# SENSEBREAST.net
KiCad netlist of a schematic drawn in EAGLE
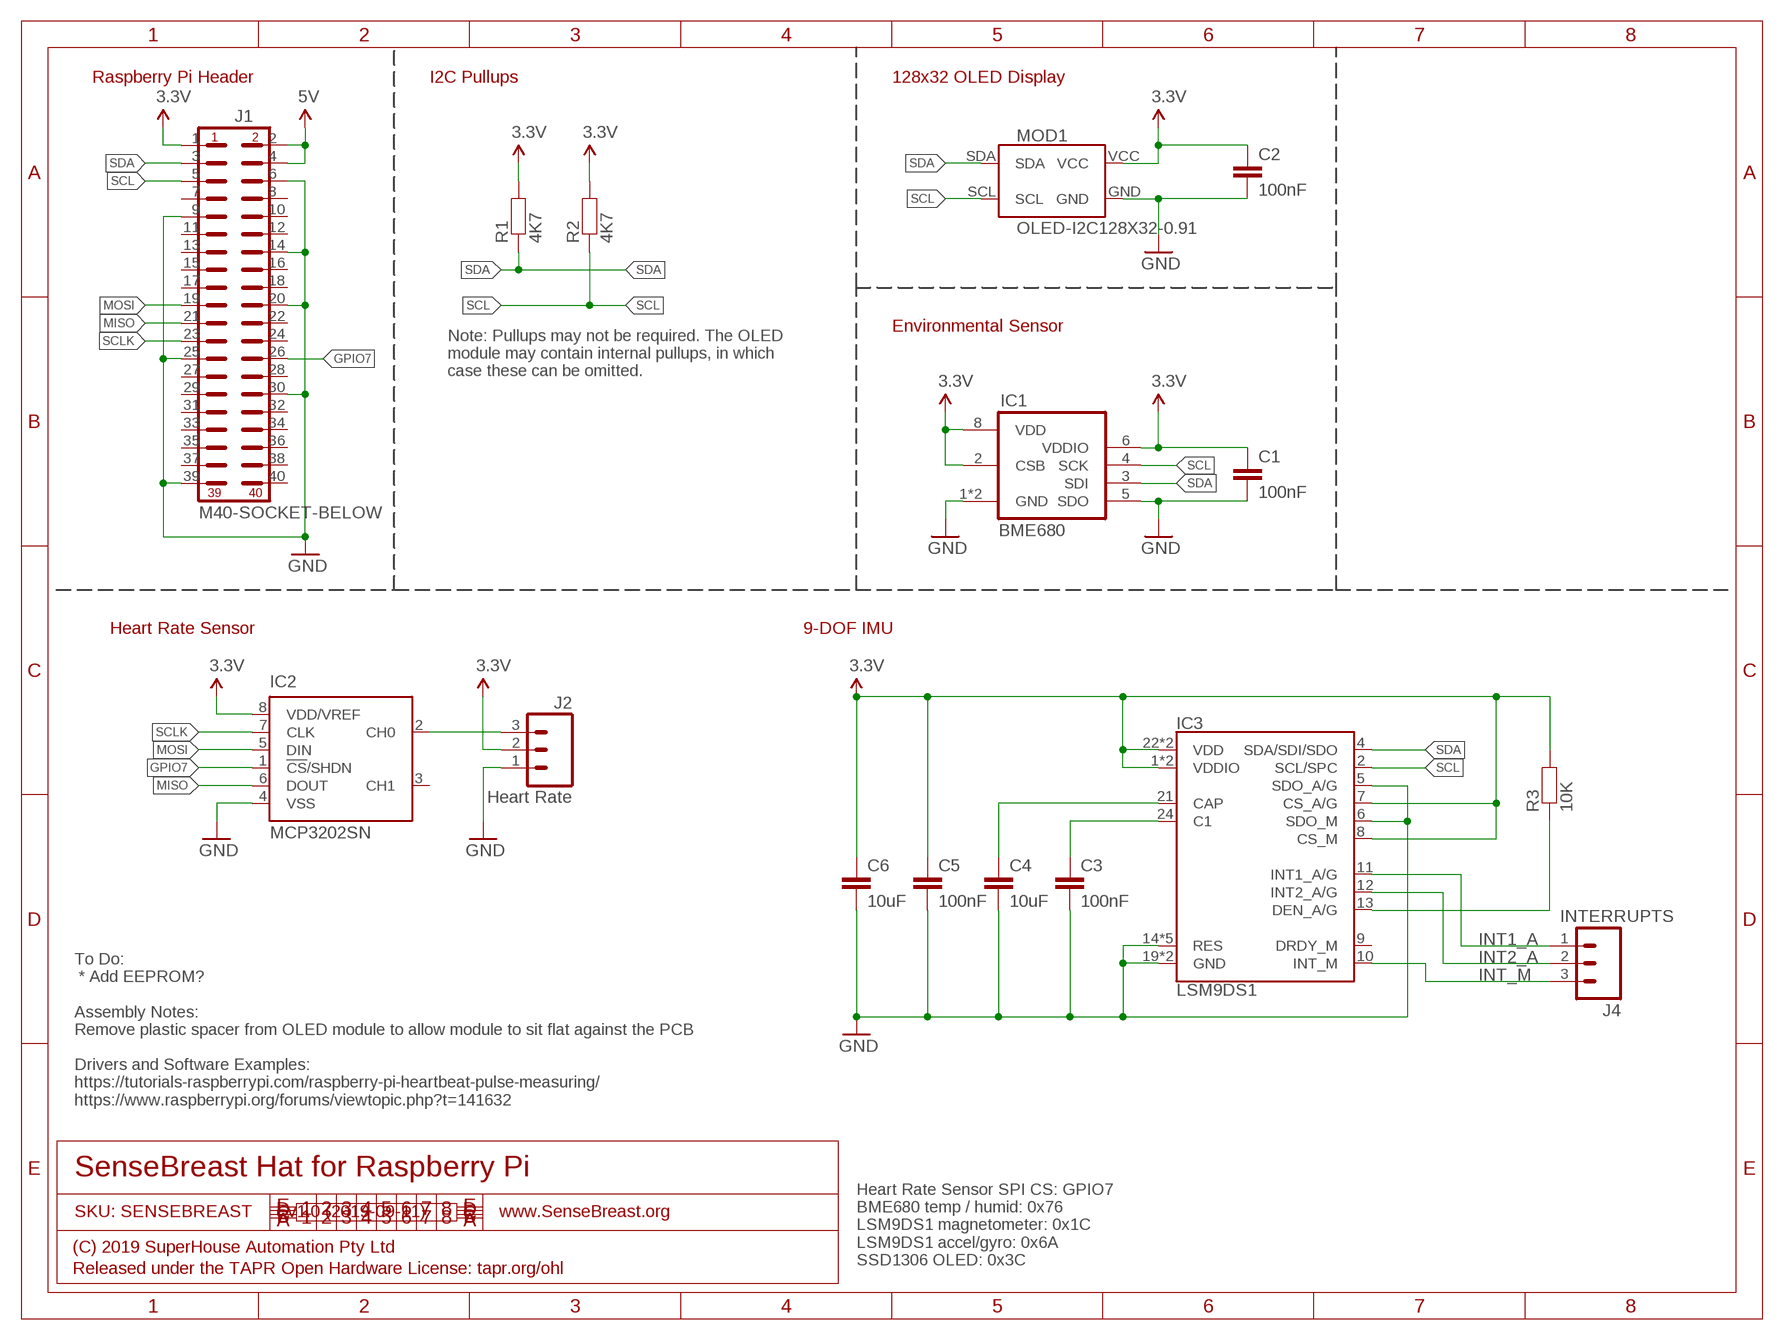
[diagram p0: schematic, sheet 1]

(export (version "E")
  (design (tool "Eeschema 10.0.6"))
  (components
    (comp (ref "C1")
      (value "100nF")
      (footprint "eagle-import:C0603")
      (libsource (lib "eagle-import") (part "CAP0603"))
    )
    (comp (ref "C2")
      (value "100nF")
      (footprint "eagle-import:C0603")
      (libsource (lib "eagle-import") (part "CAP0603"))
    )
    (comp (ref "C3")
      (value "100nF")
      (footprint "eagle-import:C0603")
      (libsource (lib "eagle-import") (part "CAP0603"))
    )
    (comp (ref "C4")
      (value "10uF")
      (footprint "eagle-import:C0805")
      (libsource (lib "eagle-import") (part "CAP0805"))
    )
    (comp (ref "C5")
      (value "100nF")
      (footprint "eagle-import:C0603")
      (libsource (lib "eagle-import") (part "CAP0603"))
    )
    (comp (ref "C6")
      (value "10uF")
      (footprint "eagle-import:C0805")
      (libsource (lib "eagle-import") (part "CAP0805"))
    )
    (comp (ref "IC1")
      (value "BME680")
      (footprint "eagle-import:BME680")
      (libsource (lib "eagle-import") (part "BME680"))
    )
    (comp (ref "IC2")
      (value "MCP3202SN")
      (footprint "eagle-import:SO-08")
      (fields (field (name "MF") "MICROCHIP") (field (name "MPN") "MCP3202-CI/SN"))
      (libsource (lib "eagle-import") (part "MCP3202SN"))
    )
    (comp (ref "IC3")
      (value "LSM9DS1")
      (footprint "eagle-import:LGA24-8X4")
      (libsource (lib "eagle-import") (part "LSM9DS1"))
    )
    (comp (ref "J1")
      (value "M40-SOCKET-BELOW")
      (footprint "eagle-import:2X20-S-BELOW")
      (libsource (lib "eagle-import") (part "M40-SOCKET-BELOW"))
    )
    (comp (ref "J2")
      (value "Heart Rate")
      (footprint "eagle-import:1X03-S-RA")
      (libsource (lib "eagle-import") (part "M03-SOCKET-RIGHTANGLE"))
    )
    (comp (ref "J4")
      (value "INTERRUPTS")
      (footprint "eagle-import:1X03")
      (libsource (lib "eagle-import") (part "M03-PLAIN"))
    )
    (comp (ref "MOD1")
      (value "OLED-I2C128X32-0.91")
      (footprint "eagle-import:OLED-128X32-0.91")
      (libsource (lib "eagle-import") (part "OLED-I2C128X32-0.91"))
    )
    (comp (ref "R1")
      (value "4K7")
      (footprint "eagle-import:R0603")
      (libsource (lib "eagle-import") (part "RESISTOR0603"))
    )
    (comp (ref "R2")
      (value "4K7")
      (footprint "eagle-import:R0603")
      (libsource (lib "eagle-import") (part "RESISTOR0603"))
    )
    (comp (ref "R3")
      (value "10K")
      (footprint "eagle-import:R0603")
      (libsource (lib "eagle-import") (part "RESISTOR0603"))
    )
  )
  (nets
    (net (code "1") (name "/INT1_A") (class "Default")
      (node (ref "IC3") (pin "11") (pinfunction "INT1_A/G_11") (pintype "bidirectional"))
      (node (ref "J4") (pin "1") (pinfunction "1_1") (pintype "passive"))
    )
    (net (code "2") (name "/INT2_A") (class "Default")
      (node (ref "IC3") (pin "12") (pinfunction "INT2_A/G_12") (pintype "bidirectional"))
      (node (ref "J4") (pin "2") (pinfunction "2_2") (pintype "passive"))
    )
    (net (code "3") (name "/INT_M") (class "Default")
      (node (ref "IC3") (pin "10") (pinfunction "INT_M_10") (pintype "bidirectional"))
      (node (ref "J4") (pin "3") (pinfunction "3_3") (pintype "passive"))
    )
    (net (code "4") (name "3.3V") (class "Default")
      (node (ref "C1") (pin "1") (pinfunction "1_1") (pintype "passive"))
      (node (ref "C2") (pin "1") (pinfunction "1_1") (pintype "passive"))
      (node (ref "C5") (pin "1") (pinfunction "1_1") (pintype "passive"))
      (node (ref "C6") (pin "1") (pinfunction "1_1") (pintype "passive"))
      (node (ref "IC1") (pin "2") (pinfunction "CSB_2") (pintype "input"))
      (node (ref "IC1") (pin "6") (pinfunction "VDDIO_6") (pintype "power_in"))
      (node (ref "IC1") (pin "8") (pinfunction "VDD_8") (pintype "power_in"))
      (node (ref "IC2") (pin "8") (pinfunction "VDD/VREF_8") (pintype "input"))
      (node (ref "IC3") (pin "1") (pinfunction "VDDIO_1") (pintype "bidirectional"))
      (node (ref "IC3") (pin "22") (pinfunction "VDD_22") (pintype "bidirectional"))
      (node (ref "IC3") (pin "23") (pinfunction "VDD_23") (pintype "bidirectional"))
      (node (ref "IC3") (pin "3") (pinfunction "VDDIO_3") (pintype "bidirectional"))
      (node (ref "IC3") (pin "7") (pinfunction "CS_A/G_7") (pintype "bidirectional"))
      (node (ref "IC3") (pin "8") (pinfunction "CS_M_8") (pintype "bidirectional"))
      (node (ref "J1") (pin "1") (pinfunction "1_1") (pintype "passive"))
      (node (ref "J2") (pin "2") (pinfunction "2_2") (pintype "passive"))
      (node (ref "MOD1") (pin "VCC") (pinfunction "VCC_VCC") (pintype "bidirectional"))
      (node (ref "R1") (pin "2") (pinfunction "2_2") (pintype "passive"))
      (node (ref "R2") (pin "2") (pinfunction "2_2") (pintype "passive"))
      (node (ref "R3") (pin "2") (pinfunction "2_2") (pintype "passive"))
    )
    (net (code "5") (name "5V") (class "Default")
      (node (ref "J1") (pin "2") (pinfunction "2_2") (pintype "passive"))
      (node (ref "J1") (pin "4") (pinfunction "4_4") (pintype "passive"))
    )
    (net (code "6") (name "GND") (class "Default")
      (node (ref "C1") (pin "2") (pinfunction "2_2") (pintype "passive"))
      (node (ref "C2") (pin "2") (pinfunction "2_2") (pintype "passive"))
      (node (ref "C3") (pin "2") (pinfunction "2_2") (pintype "passive"))
      (node (ref "C4") (pin "2") (pinfunction "2_2") (pintype "passive"))
      (node (ref "C5") (pin "2") (pinfunction "2_2") (pintype "passive"))
      (node (ref "C6") (pin "2") (pinfunction "2_2") (pintype "passive"))
      (node (ref "IC1") (pin "1") (pinfunction "GND_1") (pintype "power_in"))
      (node (ref "IC1") (pin "5") (pinfunction "SDO_5") (pintype "input"))
      (node (ref "IC1") (pin "7") (pinfunction "GND_7") (pintype "power_in"))
      (node (ref "IC2") (pin "4") (pinfunction "VSS_4") (pintype "input"))
      (node (ref "IC3") (pin "14") (pinfunction "RES_14") (pintype "bidirectional"))
      (node (ref "IC3") (pin "15") (pinfunction "RES_15") (pintype "bidirectional"))
      (node (ref "IC3") (pin "16") (pinfunction "RES_16") (pintype "bidirectional"))
      (node (ref "IC3") (pin "17") (pinfunction "RES_17") (pintype "bidirectional"))
      (node (ref "IC3") (pin "18") (pinfunction "RES_18") (pintype "bidirectional"))
      (node (ref "IC3") (pin "19") (pinfunction "GND_19") (pintype "bidirectional"))
      (node (ref "IC3") (pin "20") (pinfunction "GND_20") (pintype "bidirectional"))
      (node (ref "IC3") (pin "5") (pinfunction "SDO_A/G_5") (pintype "bidirectional"))
      (node (ref "IC3") (pin "6") (pinfunction "SDO_M_6") (pintype "bidirectional"))
      (node (ref "J1") (pin "14") (pinfunction "14_14") (pintype "passive"))
      (node (ref "J1") (pin "20") (pinfunction "20_20") (pintype "passive"))
      (node (ref "J1") (pin "25") (pinfunction "25_25") (pintype "passive"))
      (node (ref "J1") (pin "30") (pinfunction "30_30") (pintype "passive"))
      (node (ref "J1") (pin "39") (pinfunction "39_39") (pintype "passive"))
      (node (ref "J1") (pin "6") (pinfunction "6_6") (pintype "passive"))
      (node (ref "J1") (pin "9") (pinfunction "9_9") (pintype "passive"))
      (node (ref "J2") (pin "1") (pinfunction "1_1") (pintype "passive"))
      (node (ref "MOD1") (pin "GND") (pinfunction "GND_GND") (pintype "bidirectional"))
    )
    (net (code "7") (name "GPIO7") (class "Default")
      (node (ref "IC2") (pin "1") (pinfunction "~{CS}/SHDN_1") (pintype "input"))
      (node (ref "J1") (pin "26") (pinfunction "26_26") (pintype "passive"))
    )
    (net (code "8") (name "MISO") (class "Default")
      (node (ref "IC2") (pin "6") (pinfunction "DOUT_6") (pintype "input"))
      (node (ref "J1") (pin "21") (pinfunction "21_21") (pintype "passive"))
    )
    (net (code "9") (name "MOSI") (class "Default")
      (node (ref "IC2") (pin "5") (pinfunction "DIN_5") (pintype "input"))
      (node (ref "J1") (pin "19") (pinfunction "19_19") (pintype "passive"))
    )
    (net (code "10") (name "Net-(IC2-CH0)") (class "Default")
      (node (ref "IC2") (pin "2") (pinfunction "CH0_2") (pintype "input"))
      (node (ref "J2") (pin "3") (pinfunction "3_3") (pintype "passive"))
    )
    (net (code "11") (name "Net-(IC3-C1)") (class "Default")
      (node (ref "C3") (pin "1") (pinfunction "1_1") (pintype "passive"))
      (node (ref "IC3") (pin "24") (pinfunction "C1_24") (pintype "bidirectional"))
    )
    (net (code "12") (name "Net-(IC3-CAP)") (class "Default")
      (node (ref "C4") (pin "1") (pinfunction "1_1") (pintype "passive"))
      (node (ref "IC3") (pin "21") (pinfunction "CAP_21") (pintype "bidirectional"))
    )
    (net (code "13") (name "Net-(IC3-DEN_A{slash}G)") (class "Default")
      (node (ref "IC3") (pin "13") (pinfunction "DEN_A/G_13") (pintype "bidirectional"))
      (node (ref "R3") (pin "1") (pinfunction "1_1") (pintype "passive"))
    )
    (net (code "14") (name "SCL") (class "Default")
      (node (ref "IC1") (pin "4") (pinfunction "SCK_4") (pintype "bidirectional"))
      (node (ref "IC3") (pin "2") (pinfunction "SCL/SPC_2") (pintype "bidirectional"))
      (node (ref "J1") (pin "5") (pinfunction "5_5") (pintype "passive"))
      (node (ref "MOD1") (pin "SCL") (pinfunction "SCL_SCL") (pintype "bidirectional"))
      (node (ref "R2") (pin "1") (pinfunction "1_1") (pintype "passive"))
    )
    (net (code "15") (name "SCLK") (class "Default")
      (node (ref "IC2") (pin "7") (pinfunction "CLK_7") (pintype "input"))
      (node (ref "J1") (pin "23") (pinfunction "23_23") (pintype "passive"))
    )
    (net (code "16") (name "SDA") (class "Default")
      (node (ref "IC1") (pin "3") (pinfunction "SDI_3") (pintype "bidirectional"))
      (node (ref "IC3") (pin "4") (pinfunction "SDA/SDI/SDO_4") (pintype "bidirectional"))
      (node (ref "J1") (pin "3") (pinfunction "3_3") (pintype "passive"))
      (node (ref "MOD1") (pin "SDA") (pinfunction "SDA_SDA") (pintype "bidirectional"))
      (node (ref "R1") (pin "1") (pinfunction "1_1") (pintype "passive"))
    )
    (net (code "17") (name "unconnected-(IC2-CH1-Pad3)") (class "Default")
      (node (ref "IC2") (pin "3") (pinfunction "CH1_3") (pintype "input"))
    )
    (net (code "18") (name "unconnected-(IC3-DRDY_M-Pad9)") (class "Default")
      (node (ref "IC3") (pin "9") (pinfunction "DRDY_M_9") (pintype "bidirectional"))
    )
    (net (code "19") (name "unconnected-(J1-Pad7)") (class "Default")
      (node (ref "J1") (pin "7") (pinfunction "7_7") (pintype "passive"))
    )
    (net (code "20") (name "unconnected-(J1-Pad8)") (class "Default")
      (node (ref "J1") (pin "8") (pinfunction "8_8") (pintype "passive"))
    )
    (net (code "21") (name "unconnected-(J1-Pad10)") (class "Default")
      (node (ref "J1") (pin "10") (pinfunction "10_10") (pintype "passive"))
    )
    (net (code "22") (name "unconnected-(J1-Pad11)") (class "Default")
      (node (ref "J1") (pin "11") (pinfunction "11_11") (pintype "passive"))
    )
    (net (code "23") (name "unconnected-(J1-Pad12)") (class "Default")
      (node (ref "J1") (pin "12") (pinfunction "12_12") (pintype "passive"))
    )
    (net (code "24") (name "unconnected-(J1-Pad13)") (class "Default")
      (node (ref "J1") (pin "13") (pinfunction "13_13") (pintype "passive"))
    )
    (net (code "25") (name "unconnected-(J1-Pad15)") (class "Default")
      (node (ref "J1") (pin "15") (pinfunction "15_15") (pintype "passive"))
    )
    (net (code "26") (name "unconnected-(J1-Pad16)") (class "Default")
      (node (ref "J1") (pin "16") (pinfunction "16_16") (pintype "passive"))
    )
    (net (code "27") (name "unconnected-(J1-Pad17)") (class "Default")
      (node (ref "J1") (pin "17") (pinfunction "17_17") (pintype "passive"))
    )
    (net (code "28") (name "unconnected-(J1-Pad18)") (class "Default")
      (node (ref "J1") (pin "18") (pinfunction "18_18") (pintype "passive"))
    )
    (net (code "29") (name "unconnected-(J1-Pad22)") (class "Default")
      (node (ref "J1") (pin "22") (pinfunction "22_22") (pintype "passive"))
    )
    (net (code "30") (name "unconnected-(J1-Pad24)") (class "Default")
      (node (ref "J1") (pin "24") (pinfunction "24_24") (pintype "passive"))
    )
    (net (code "31") (name "unconnected-(J1-Pad27)") (class "Default")
      (node (ref "J1") (pin "27") (pinfunction "27_27") (pintype "passive"))
    )
    (net (code "32") (name "unconnected-(J1-Pad28)") (class "Default")
      (node (ref "J1") (pin "28") (pinfunction "28_28") (pintype "passive"))
    )
    (net (code "33") (name "unconnected-(J1-Pad29)") (class "Default")
      (node (ref "J1") (pin "29") (pinfunction "29_29") (pintype "passive"))
    )
    (net (code "34") (name "unconnected-(J1-Pad31)") (class "Default")
      (node (ref "J1") (pin "31") (pinfunction "31_31") (pintype "passive"))
    )
    (net (code "35") (name "unconnected-(J1-Pad32)") (class "Default")
      (node (ref "J1") (pin "32") (pinfunction "32_32") (pintype "passive"))
    )
    (net (code "36") (name "unconnected-(J1-Pad33)") (class "Default")
      (node (ref "J1") (pin "33") (pinfunction "33_33") (pintype "passive"))
    )
    (net (code "37") (name "unconnected-(J1-Pad34)") (class "Default")
      (node (ref "J1") (pin "34") (pinfunction "34_34") (pintype "passive"))
    )
    (net (code "38") (name "unconnected-(J1-Pad35)") (class "Default")
      (node (ref "J1") (pin "35") (pinfunction "35_35") (pintype "passive"))
    )
    (net (code "39") (name "unconnected-(J1-Pad36)") (class "Default")
      (node (ref "J1") (pin "36") (pinfunction "36_36") (pintype "passive"))
    )
    (net (code "40") (name "unconnected-(J1-Pad37)") (class "Default")
      (node (ref "J1") (pin "37") (pinfunction "37_37") (pintype "passive"))
    )
    (net (code "41") (name "unconnected-(J1-Pad38)") (class "Default")
      (node (ref "J1") (pin "38") (pinfunction "38_38") (pintype "passive"))
    )
    (net (code "42") (name "unconnected-(J1-Pad40)") (class "Default")
      (node (ref "J1") (pin "40") (pinfunction "40_40") (pintype "passive"))
    )
  )
)
